# scheme.net
KiCad netlist of a schematic drawn in EAGLE
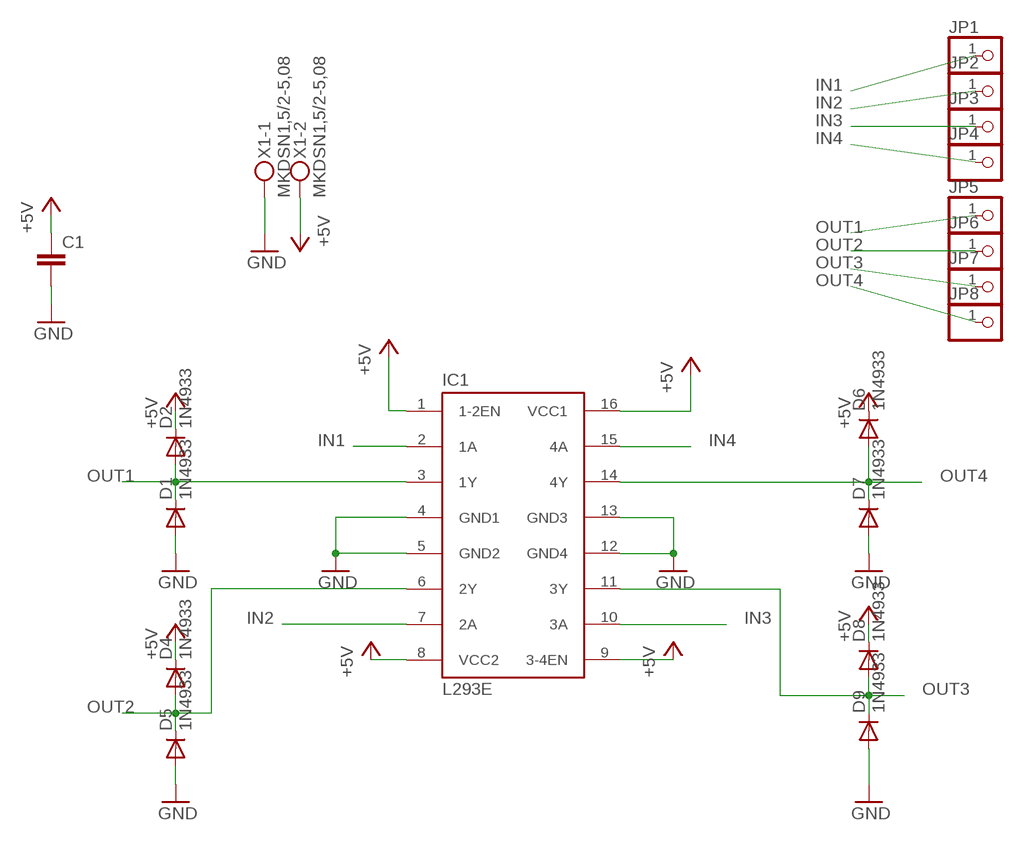
[diagram p0: schematic, sheet 1]

(export (version "E")
  (design (tool "Eeschema 10.0.6"))
  (components
    (comp (ref "C1")
      (value "C-EUC0805K")
      (footprint "eagle-import:C0805K")
      (libsource (lib "eagle-import") (part "C-EUC0805K"))
    )
    (comp (ref "D1")
      (value "1N4933")
      (footprint "eagle-import:DO41-10")
      (libsource (lib "eagle-import") (part "1N4933"))
    )
    (comp (ref "D2")
      (value "1N4933")
      (footprint "eagle-import:DO41-10")
      (libsource (lib "eagle-import") (part "1N4933"))
    )
    (comp (ref "D4")
      (value "1N4933")
      (footprint "eagle-import:DO41-10")
      (libsource (lib "eagle-import") (part "1N4933"))
    )
    (comp (ref "D5")
      (value "1N4933")
      (footprint "eagle-import:DO41-10")
      (libsource (lib "eagle-import") (part "1N4933"))
    )
    (comp (ref "D6")
      (value "1N4933")
      (footprint "eagle-import:DO41-10")
      (libsource (lib "eagle-import") (part "1N4933"))
    )
    (comp (ref "D7")
      (value "1N4933")
      (footprint "eagle-import:DO41-10")
      (libsource (lib "eagle-import") (part "1N4933"))
    )
    (comp (ref "D8")
      (value "1N4933")
      (footprint "eagle-import:DO41-10")
      (libsource (lib "eagle-import") (part "1N4933"))
    )
    (comp (ref "D9")
      (value "1N4933")
      (footprint "eagle-import:DO41-10")
      (libsource (lib "eagle-import") (part "1N4933"))
    )
    (comp (ref "IC1")
      (value "L293E")
      (footprint "eagle-import:DIL16")
      (fields (field (name "MF") "Arrow Electronics"))
      (libsource (lib "eagle-import") (part "L293E"))
    )
    (comp (ref "JP1")
      (value "PINHD-1X1")
      (footprint "eagle-import:1X01")
      (libsource (lib "eagle-import") (part "PINHD-1X1"))
    )
    (comp (ref "JP2")
      (value "PINHD-1X1")
      (footprint "eagle-import:1X01")
      (libsource (lib "eagle-import") (part "PINHD-1X1"))
    )
    (comp (ref "JP3")
      (value "PINHD-1X1")
      (footprint "eagle-import:1X01")
      (libsource (lib "eagle-import") (part "PINHD-1X1"))
    )
    (comp (ref "JP4")
      (value "PINHD-1X1")
      (footprint "eagle-import:1X01")
      (libsource (lib "eagle-import") (part "PINHD-1X1"))
    )
    (comp (ref "JP5")
      (value "PINHD-1X1")
      (footprint "eagle-import:1X01")
      (libsource (lib "eagle-import") (part "PINHD-1X1"))
    )
    (comp (ref "JP6")
      (value "PINHD-1X1")
      (footprint "eagle-import:1X01")
      (libsource (lib "eagle-import") (part "PINHD-1X1"))
    )
    (comp (ref "JP7")
      (value "PINHD-1X1")
      (footprint "eagle-import:1X01")
      (libsource (lib "eagle-import") (part "PINHD-1X1"))
    )
    (comp (ref "JP8")
      (value "PINHD-1X1")
      (footprint "eagle-import:1X01")
      (libsource (lib "eagle-import") (part "PINHD-1X1"))
    )
    (comp (ref "X1")
      (value "MKDSN1,5/2-5,08")
      (footprint "eagle-import:MKDSN1,5_2-5,08")
      (fields (field (name "MPN") "MKDSN 1,5/2-5.08"))
      (libsource (lib "eagle-import") (part "MKDSN1,5/2-5,08"))
    )
  )
  (nets
    (net (code "1") (name "+5V") (class "Default")
      (node (ref "C1") (pin "1") (pinfunction "1_1") (pintype "passive"))
      (node (ref "D2") (pin "C") (pinfunction "C_C") (pintype "passive"))
      (node (ref "D4") (pin "C") (pinfunction "C_C") (pintype "passive"))
      (node (ref "D6") (pin "C") (pinfunction "C_C") (pintype "passive"))
      (node (ref "D8") (pin "C") (pinfunction "C_C") (pintype "passive"))
      (node (ref "IC1") (pin "1") (pinfunction "1-2EN_1") (pintype "input"))
      (node (ref "IC1") (pin "16") (pinfunction "VCC1_16") (pintype "power_in"))
      (node (ref "IC1") (pin "8") (pinfunction "VCC2_8") (pintype "power_in"))
      (node (ref "IC1") (pin "9") (pinfunction "3-4EN_9") (pintype "input"))
      (node (ref "X1") (pin "2") (pinfunction "KL_2") (pintype "passive"))
    )
    (net (code "2") (name "/IN1") (class "Default")
      (node (ref "IC1") (pin "2") (pinfunction "1A_2") (pintype "input"))
      (node (ref "JP1") (pin "1") (pinfunction "1_1") (pintype "passive"))
    )
    (net (code "3") (name "/IN2") (class "Default")
      (node (ref "IC1") (pin "7") (pinfunction "2A_7") (pintype "input"))
      (node (ref "JP2") (pin "1") (pinfunction "1_1") (pintype "passive"))
    )
    (net (code "4") (name "/IN3") (class "Default")
      (node (ref "IC1") (pin "10") (pinfunction "3A_10") (pintype "input"))
      (node (ref "JP3") (pin "1") (pinfunction "1_1") (pintype "passive"))
    )
    (net (code "5") (name "/IN4") (class "Default")
      (node (ref "IC1") (pin "15") (pinfunction "4A_15") (pintype "input"))
      (node (ref "JP4") (pin "1") (pinfunction "1_1") (pintype "passive"))
    )
    (net (code "6") (name "/OUT1") (class "Default")
      (node (ref "D1") (pin "C") (pinfunction "C_C") (pintype "passive"))
      (node (ref "D2") (pin "A") (pinfunction "A_A") (pintype "passive"))
      (node (ref "IC1") (pin "3") (pinfunction "1Y_3") (pintype "output"))
      (node (ref "JP5") (pin "1") (pinfunction "1_1") (pintype "passive"))
    )
    (net (code "7") (name "/OUT2") (class "Default")
      (node (ref "D4") (pin "A") (pinfunction "A_A") (pintype "passive"))
      (node (ref "D5") (pin "C") (pinfunction "C_C") (pintype "passive"))
      (node (ref "IC1") (pin "6") (pinfunction "2Y_6") (pintype "output"))
      (node (ref "JP6") (pin "1") (pinfunction "1_1") (pintype "passive"))
    )
    (net (code "8") (name "/OUT3") (class "Default")
      (node (ref "D8") (pin "A") (pinfunction "A_A") (pintype "passive"))
      (node (ref "D9") (pin "C") (pinfunction "C_C") (pintype "passive"))
      (node (ref "IC1") (pin "11") (pinfunction "3Y_11") (pintype "output"))
      (node (ref "JP7") (pin "1") (pinfunction "1_1") (pintype "passive"))
    )
    (net (code "9") (name "/OUT4") (class "Default")
      (node (ref "D6") (pin "A") (pinfunction "A_A") (pintype "passive"))
      (node (ref "D7") (pin "C") (pinfunction "C_C") (pintype "passive"))
      (node (ref "IC1") (pin "14") (pinfunction "4Y_14") (pintype "output"))
      (node (ref "JP8") (pin "1") (pinfunction "1_1") (pintype "passive"))
    )
    (net (code "10") (name "GND") (class "Default")
      (node (ref "C1") (pin "2") (pinfunction "2_2") (pintype "passive"))
      (node (ref "D1") (pin "A") (pinfunction "A_A") (pintype "passive"))
      (node (ref "D5") (pin "A") (pinfunction "A_A") (pintype "passive"))
      (node (ref "D7") (pin "A") (pinfunction "A_A") (pintype "passive"))
      (node (ref "D9") (pin "A") (pinfunction "A_A") (pintype "passive"))
      (node (ref "IC1") (pin "12") (pinfunction "GND4_12") (pintype "power_in"))
      (node (ref "IC1") (pin "13") (pinfunction "GND3_13") (pintype "power_in"))
      (node (ref "IC1") (pin "4") (pinfunction "GND1_4") (pintype "power_in"))
      (node (ref "IC1") (pin "5") (pinfunction "GND2_5") (pintype "power_in"))
      (node (ref "X1") (pin "1") (pinfunction "KL_1") (pintype "passive"))
    )
  )
)
